# encoder-switch-type1-tht.net
KiCad netlist of a schematic drawn in EAGLE
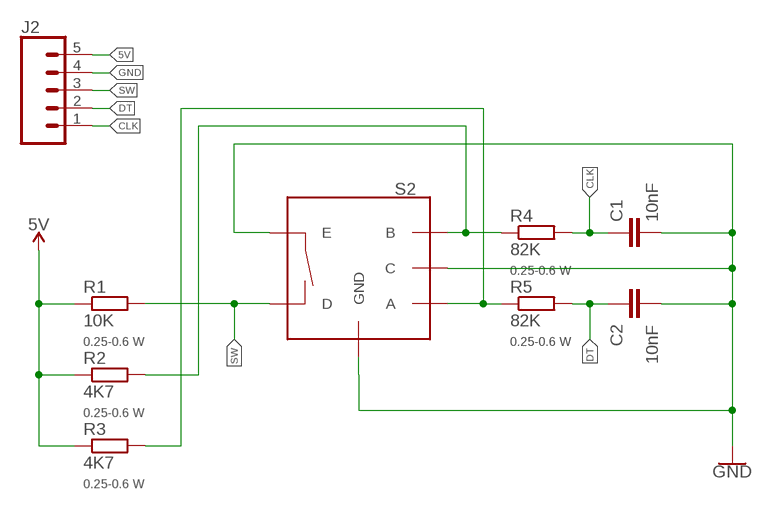
[diagram p0: schematic, sheet 1]

(export (version "E")
  (design (tool "Eeschema 10.0.6"))
  (components
    (comp (ref "C1")
      (value "10nF")
      (footprint "eagle-import:C025-024X044")
      (libsource (lib "eagle-import") (part "CAPACITOR_1025-024X044"))
    )
    (comp (ref "C2")
      (value "10nF")
      (footprint "eagle-import:C025-024X044")
      (libsource (lib "eagle-import") (part "CAPACITOR_1025-024X044"))
    )
    (comp (ref "J2")
      (value "CONN_051X05LA")
      (footprint "eagle-import:1X05_90")
      (libsource (lib "eagle-import") (part "CONN_051X05LA"))
    )
    (comp (ref "R1")
      (value "10K")
      (footprint "eagle-import:0204V")
      (fields (field (name "POWER") "0.25-0.6 W"))
      (libsource (lib "eagle-import") (part "RESISTOR0204/2V"))
    )
    (comp (ref "R2")
      (value "4K7")
      (footprint "eagle-import:0204V")
      (fields (field (name "POWER") "0.25-0.6 W"))
      (libsource (lib "eagle-import") (part "RESISTOR0204/2V"))
    )
    (comp (ref "R3")
      (value "4K7")
      (footprint "eagle-import:0204V")
      (fields (field (name "POWER") "0.25-0.6 W"))
      (libsource (lib "eagle-import") (part "RESISTOR0204/2V"))
    )
    (comp (ref "R4")
      (value "82K")
      (footprint "eagle-import:0204V")
      (fields (field (name "POWER") "0.25-0.6 W"))
      (libsource (lib "eagle-import") (part "RESISTOR0204/2V"))
    )
    (comp (ref "R5")
      (value "82K")
      (footprint "eagle-import:0204V")
      (fields (field (name "POWER") "0.25-0.6 W"))
      (libsource (lib "eagle-import") (part "RESISTOR0204/2V"))
    )
    (comp (ref "S2")
      (value "ENCODER_SWITCH")
      (footprint "eagle-import:ROTARY_ENC_PLAIN")
      (libsource (lib "eagle-import") (part "ENCODER_SWITCH"))
    )
  )
  (nets
    (net (code "1") (name "5V") (class "Default")
      (node (ref "J2") (pin "5") (pinfunction "5_5") (pintype "passive"))
      (node (ref "R1") (pin "1") (pinfunction "1_1") (pintype "passive"))
      (node (ref "R2") (pin "1") (pinfunction "1_1") (pintype "passive"))
      (node (ref "R3") (pin "1") (pinfunction "1_1") (pintype "passive"))
    )
    (net (code "2") (name "CLK") (class "Default")
      (node (ref "C1") (pin "1") (pinfunction "1_1") (pintype "passive"))
      (node (ref "J2") (pin "1") (pinfunction "1_1") (pintype "passive"))
      (node (ref "R4") (pin "2") (pinfunction "2_2") (pintype "passive"))
    )
    (net (code "3") (name "DT") (class "Default")
      (node (ref "C2") (pin "1") (pinfunction "1_1") (pintype "passive"))
      (node (ref "J2") (pin "2") (pinfunction "2_2") (pintype "passive"))
      (node (ref "R5") (pin "2") (pinfunction "2_2") (pintype "passive"))
    )
    (net (code "4") (name "GND") (class "Default")
      (node (ref "C1") (pin "2") (pinfunction "2_2") (pintype "passive"))
      (node (ref "C2") (pin "2") (pinfunction "2_2") (pintype "passive"))
      (node (ref "J2") (pin "4") (pinfunction "4_4") (pintype "passive"))
      (node (ref "S2") (pin "C") (pinfunction "C_C") (pintype "bidirectional"))
      (node (ref "S2") (pin "E") (pinfunction "E_E") (pintype "bidirectional"))
      (node (ref "S2") (pin "GND1") (pinfunction "GND_GND1") (pintype "bidirectional"))
      (node (ref "S2") (pin "GND2") (pinfunction "GND_GND2") (pintype "bidirectional"))
    )
    (net (code "5") (name "Net-(R2-Pad2)") (class "Default")
      (node (ref "R2") (pin "2") (pinfunction "2_2") (pintype "passive"))
      (node (ref "R4") (pin "1") (pinfunction "1_1") (pintype "passive"))
      (node (ref "S2") (pin "B") (pinfunction "B_B") (pintype "bidirectional"))
    )
    (net (code "6") (name "Net-(R3-Pad2)") (class "Default")
      (node (ref "R3") (pin "2") (pinfunction "2_2") (pintype "passive"))
      (node (ref "R5") (pin "1") (pinfunction "1_1") (pintype "passive"))
      (node (ref "S2") (pin "A") (pinfunction "A_A") (pintype "bidirectional"))
    )
    (net (code "7") (name "SW") (class "Default")
      (node (ref "J2") (pin "3") (pinfunction "3_3") (pintype "passive"))
      (node (ref "R1") (pin "2") (pinfunction "2_2") (pintype "passive"))
      (node (ref "S2") (pin "D") (pinfunction "D_D") (pintype "bidirectional"))
    )
  )
)
